# LPCB235_-_POWER_MANAGEMENT.net
KiCad netlist of a schematic drawn in Altium Designer
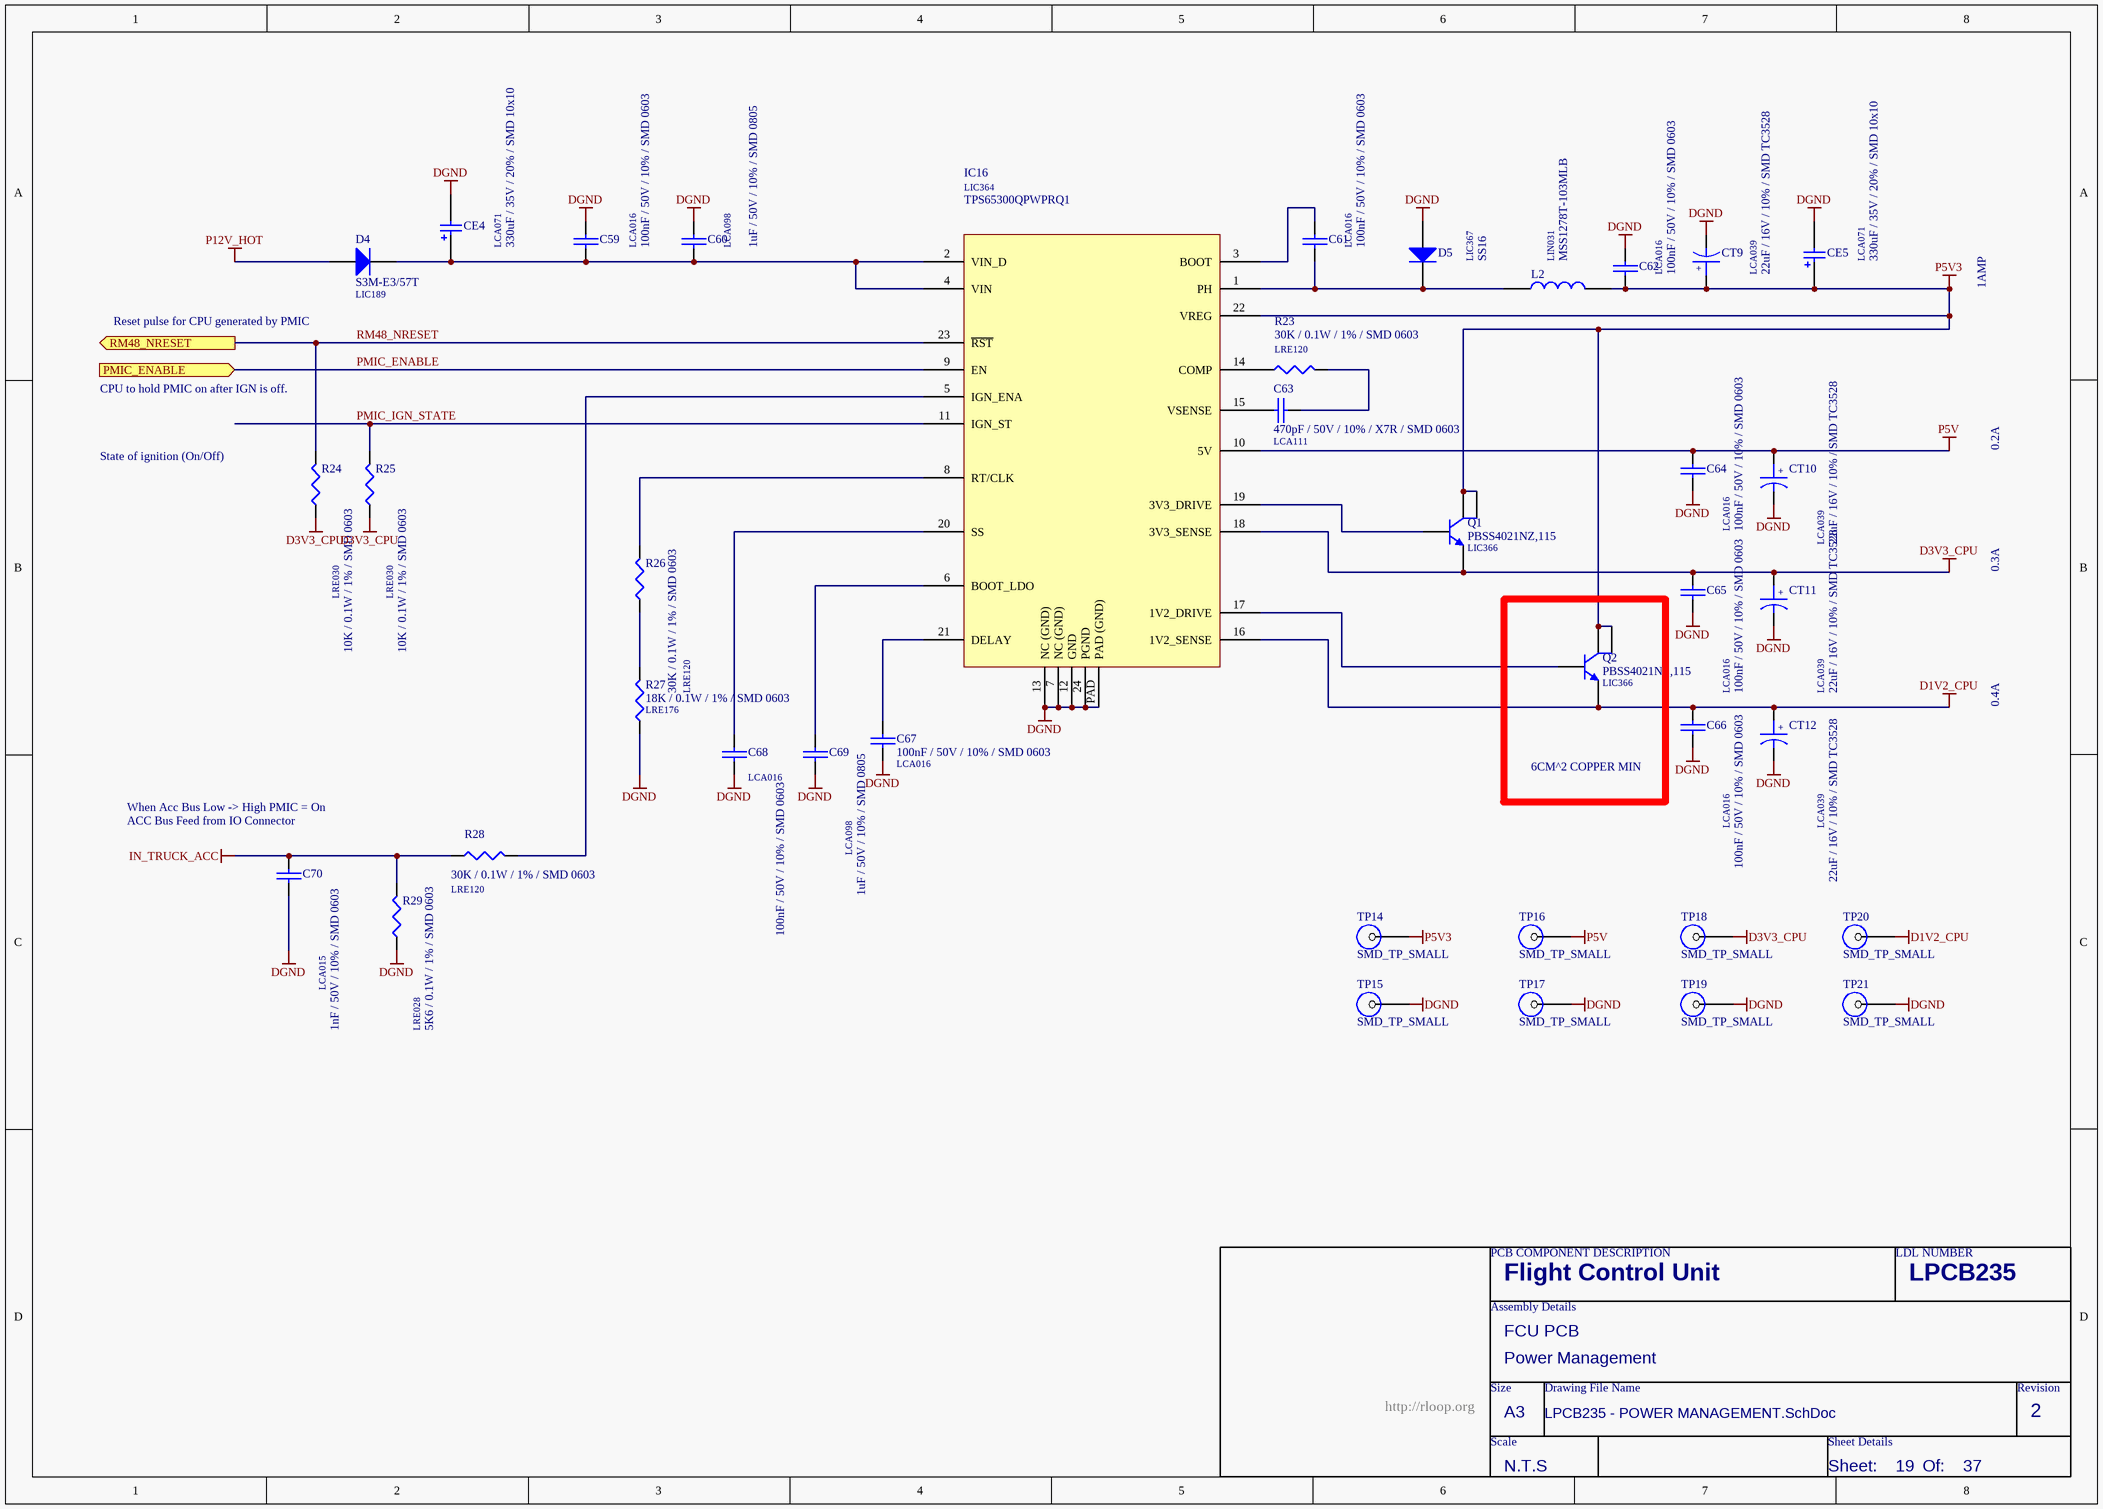
[diagram p0: LPCB235 - POWER MANAGEMENT.SchDoc]

(export (version "E")
  (design (tool "Eeschema 10.0.6"))
  (components
    (comp (ref "C59")
      (value "100nF / 50V / 10% / SMD 0603")
      (footprint "LFP011__CC1608-0603-IPC7351_B")
      (description "Capacitor, Ceramic Chip, 100nF (0.1uF), 50V, 5%, SMD 0603 [LCA016]")
      (fields (field (name "LDL_NUMBER") "LCA016"))
      (libsource (lib "LDL_Capacitors") (part "100nF / 50V / 10% / SMD 0603"))
    )
    (comp (ref "C60")
      (value "1uF / 50V / 10% / SMD 0805")
      (footprint "LFP010__CC2012-0805-IPC7351_B")
      (description "Capacitor, Ceramic Chip, 1uF, 50V, SMD 0805 [LCA098]")
      (fields (field (name "LDL_NUMBER") "LCA098"))
      (libsource (lib "LDL_Capacitors") (part "1uF / 50V / 10% / SMD 0805"))
    )
    (comp (ref "C61")
      (value "100nF / 50V / 10% / SMD 0603")
      (footprint "LFP011__CC1608-0603-IPC7351_B")
      (description "Capacitor, Ceramic Chip, 100nF (0.1uF), 50V, 5%, SMD 0603 [LCA016]")
      (fields (field (name "LDL_NUMBER") "LCA016"))
      (libsource (lib "LDL_Capacitors") (part "100nF / 50V / 10% / SMD 0603"))
    )
    (comp (ref "C62")
      (value "100nF / 50V / 10% / SMD 0603")
      (footprint "LFP011__CC1608-0603-IPC7351_B")
      (description "Capacitor, Ceramic Chip, 100nF (0.1uF), 50V, 5%, SMD 0603 [LCA016]")
      (fields (field (name "LDL_NUMBER") "LCA016"))
      (libsource (lib "LDL_Capacitors") (part "100nF / 50V / 10% / SMD 0603"))
    )
    (comp (ref "C63")
      (value "470pF / 50V / 10% / X7R / SMD 0603")
      (footprint "LFP011__CC1608-0603-IPC7351_B")
      (description "Capacitor, Ceramic Chip, 470pF, 50V, 10% X7R, SMD 0603 [LCA111]")
      (fields (field (name "LDL_NUMBER") "LCA111"))
      (libsource (lib "LDL_Capacitors") (part "470pF / 50V / 10% / X7R / SMD 0603"))
    )
    (comp (ref "C64")
      (value "100nF / 50V / 10% / SMD 0603")
      (footprint "LFP011__CC1608-0603-IPC7351_B")
      (description "Capacitor, Ceramic Chip, 100nF (0.1uF), 50V, 5%, SMD 0603 [LCA016]")
      (fields (field (name "LDL_NUMBER") "LCA016"))
      (libsource (lib "LDL_Capacitors") (part "100nF / 50V / 10% / SMD 0603"))
    )
    (comp (ref "C65")
      (value "100nF / 50V / 10% / SMD 0603")
      (footprint "LFP011__CC1608-0603-IPC7351_B")
      (description "Capacitor, Ceramic Chip, 100nF (0.1uF), 50V, 5%, SMD 0603 [LCA016]")
      (fields (field (name "LDL_NUMBER") "LCA016"))
      (libsource (lib "LDL_Capacitors") (part "100nF / 50V / 10% / SMD 0603"))
    )
    (comp (ref "C66")
      (value "100nF / 50V / 10% / SMD 0603")
      (footprint "LFP011__CC1608-0603-IPC7351_B")
      (description "Capacitor, Ceramic Chip, 100nF (0.1uF), 50V, 5%, SMD 0603 [LCA016]")
      (fields (field (name "LDL_NUMBER") "LCA016"))
      (libsource (lib "LDL_Capacitors") (part "100nF / 50V / 10% / SMD 0603"))
    )
    (comp (ref "C67")
      (value "100nF / 50V / 10% / SMD 0603")
      (footprint "LFP011__CC1608-0603-IPC7351_B")
      (description "Capacitor, Ceramic Chip, 100nF (0.1uF), 50V, 5%, SMD 0603 [LCA016]")
      (fields (field (name "LDL_NUMBER") "LCA016"))
      (libsource (lib "LDL_Capacitors") (part "100nF / 50V / 10% / SMD 0603"))
    )
    (comp (ref "C68")
      (value "100nF / 50V / 10% / SMD 0603")
      (footprint "LFP011__CC1608-0603-IPC7351_B")
      (description "Capacitor, Ceramic Chip, 100nF (0.1uF), 50V, 5%, SMD 0603 [LCA016]")
      (fields (field (name "LDL_NUMBER") "LCA016"))
      (libsource (lib "LDL_Capacitors") (part "100nF / 50V / 10% / SMD 0603"))
    )
    (comp (ref "C69")
      (value "1uF / 50V / 10% / SMD 0805")
      (footprint "LFP010__CC2012-0805-IPC7351_B")
      (description "Capacitor, Ceramic Chip, 1uF, 50V, SMD 0805 [LCA098]")
      (fields (field (name "LDL_NUMBER") "LCA098"))
      (libsource (lib "LDL_Capacitors") (part "1uF / 50V / 10% / SMD 0805"))
    )
    (comp (ref "C70")
      (value "1nF / 50V / 10% / SMD 0603")
      (footprint "LFP011__CC1608-0603-IPC7351_B")
      (description "Capacitor, Ceramic Chip, 1nF (1000pF), 50V, 10%, SMD 0603 [LCA015]")
      (fields (field (name "LDL_NUMBER") "LCA015"))
      (libsource (lib "LDL_Capacitors") (part "1nF / 50V / 10% / SMD 0603"))
    )
    (comp (ref "CE4")
      (value "330uF / 35V / 20% / SMD 10x10")
      (footprint "LFP041__NICHICON_WT_10X10")
      (description "Capacitor, Aluminum Electrolytic, 330uF, 35V, 20%, SMD (10mm x 10mm)")
      (fields (field (name "LDL_NUMBER") "LCA071"))
      (libsource (lib "LDL_Capacitors") (part "330uF / 35V / 20% / SMD 10x10"))
    )
    (comp (ref "CE5")
      (value "330uF / 35V / 20% / SMD 10x10")
      (footprint "LFP041__NICHICON_WT_10X10")
      (description "Capacitor, Aluminum Electrolytic, 330uF, 35V, 20%, SMD (10mm x 10mm)")
      (fields (field (name "LDL_NUMBER") "LCA071"))
      (libsource (lib "LDL_Capacitors") (part "330uF / 35V / 20% / SMD 10x10"))
    )
    (comp (ref "CT9")
      (value "22uF / 16V / 10% / SMD TC3528")
      (footprint "LFP018__TC3528")
      (description "Capacitor, Tantalum, 22uF, 16V, 10%, SMD TC3528 (BCASE) [LCA039]")
      (fields (field (name "LDL_NUMBER") "LCA039"))
      (libsource (lib "LDL_Capacitors") (part "22uF / 16V / 10% / SMD TC3528"))
    )
    (comp (ref "CT10")
      (value "22uF / 16V / 10% / SMD TC3528")
      (footprint "LFP018__TC3528")
      (description "Capacitor, Tantalum, 22uF, 16V, 10%, SMD TC3528 (BCASE) [LCA039]")
      (fields (field (name "LDL_NUMBER") "LCA039"))
      (libsource (lib "LDL_Capacitors") (part "22uF / 16V / 10% / SMD TC3528"))
    )
    (comp (ref "CT11")
      (value "22uF / 16V / 10% / SMD TC3528")
      (footprint "LFP018__TC3528")
      (description "Capacitor, Tantalum, 22uF, 16V, 10%, SMD TC3528 (BCASE) [LCA039]")
      (fields (field (name "LDL_NUMBER") "LCA039"))
      (libsource (lib "LDL_Capacitors") (part "22uF / 16V / 10% / SMD TC3528"))
    )
    (comp (ref "CT12")
      (value "22uF / 16V / 10% / SMD TC3528")
      (footprint "LFP018__TC3528")
      (description "Capacitor, Tantalum, 22uF, 16V, 10%, SMD TC3528 (BCASE) [LCA039]")
      (fields (field (name "LDL_NUMBER") "LCA039"))
      (libsource (lib "LDL_Capacitors") (part "22uF / 16V / 10% / SMD TC3528"))
    )
    (comp (ref "D4")
      (value "S3M-E3/57T")
      (footprint "LFP040__DO-214AB")
      (description "Diode, General Purpose Rectifier, 3A, 200V, SMD DO-214AB [LIC189]")
      (fields (field (name "LDL_NUMBER") "LIC189"))
      (libsource (lib "LDL_Semiconductors") (part "S3M-E3/57T"))
    )
    (comp (ref "D5")
      (value "SS16")
      (footprint "LFP039__DO-214AC")
      (description "Diode, Schottky Rectifier, 60V, 1A, SMD DO-214AC [LIC367]")
      (fields (field (name "LDL_NUMBER") "LIC367"))
      (libsource (lib "LDL_Semiconductors") (part "SS16"))
    )
    (comp (ref "IC16")
      (value "TPS65300QPWPRQ1")
      (footprint "LFP036__R-PDSO-G24")
      (description "IC, Power Management IC, SMD [LIC364]")
      (fields (field (name "LDL_NUMBER") "LIC364"))
      (libsource (lib "LDL_Semiconductors") (part "TPS65300QPWPRQ1"))
    )
    (comp (ref "L2")
      (value "MSS1278T-103MLB")
      (footprint "LFP037__MSS1278T")
      (description "Inductor, 10uH, 20%, 5.7A, SMD [LIN031]")
      (fields (field (name "LDL_NUMBER") "LIN031"))
      (libsource (lib "LDL_Inductors") (part "MSS1278T-103MLB"))
    )
    (comp (ref "Q1")
      (value "PBSS4021NZ,115")
      (footprint "LFP038__SOT223-4M")
      (description "Transistor, NPN, 20V 8A 770mW 95MHz, SMD [LIC366]")
      (fields (field (name "LDL_NUMBER") "LIC366"))
      (libsource (lib "LDL_Semiconductors") (part "PBSS4021NZ,115"))
    )
    (comp (ref "Q2")
      (value "PBSS4021NZ,115")
      (footprint "LFP038__SOT223-4M")
      (description "Transistor, NPN, 20V 8A 770mW 95MHz, SMD [LIC366]")
      (fields (field (name "LDL_NUMBER") "LIC366"))
      (libsource (lib "LDL_Semiconductors") (part "PBSS4021NZ,115"))
    )
    (comp (ref "R23")
      (value "30K / 0.1W / 1% / SMD 0603")
      (footprint "LFP020__CR1608-0603-IPC7351_B")
      (description "Resistor, Ceramic Chip, 30K, 0.1W, 1%, SMD 0603 [LRE120]")
      (fields (field (name "LDL_NUMBER") "LRE120"))
      (libsource (lib "LDL_Resistors") (part "30K / 0.1W / 1% / SMD 0603"))
    )
    (comp (ref "R24")
      (value "10K / 0.1W / 1% / SMD 0603")
      (footprint "LFP020__CR1608-0603-IPC7351_B")
      (description "Resistor, Ceramic Chip, 10K, 0.1W, 1%, SMD 0603 [LRE030]")
      (fields (field (name "LDL_NUMBER") "LRE030"))
      (libsource (lib "LDL_Resistors") (part "10K / 0.1W / 1% / SMD 0603"))
    )
    (comp (ref "R25")
      (value "10K / 0.1W / 1% / SMD 0603")
      (footprint "LFP020__CR1608-0603-IPC7351_B")
      (description "Resistor, Ceramic Chip, 10K, 0.1W, 1%, SMD 0603 [LRE030]")
      (fields (field (name "LDL_NUMBER") "LRE030"))
      (libsource (lib "LDL_Resistors") (part "10K / 0.1W / 1% / SMD 0603"))
    )
    (comp (ref "R26")
      (value "30K / 0.1W / 1% / SMD 0603")
      (footprint "LFP020__CR1608-0603-IPC7351_B")
      (description "Resistor, Ceramic Chip, 30K, 0.1W, 1%, SMD 0603 [LRE120]")
      (fields (field (name "LDL_NUMBER") "LRE120"))
      (libsource (lib "LDL_Resistors") (part "30K / 0.1W / 1% / SMD 0603"))
    )
    (comp (ref "R27")
      (value "18K / 0.1W / 1% / SMD 0603")
      (footprint "LFP020__CR1608-0603-IPC7351_B")
      (description "Resistor, Ceramic Chip, 18K, 0.1W, 1%, SMD 0603 [LRE176]")
      (fields (field (name "LDL_NUMBER") "LRE176"))
      (libsource (lib "LDL_Resistors") (part "18K / 0.1W / 1% / SMD 0603"))
    )
    (comp (ref "R28")
      (value "30K / 0.1W / 1% / SMD 0603")
      (footprint "LFP020__CR1608-0603-IPC7351_B")
      (description "Resistor, Ceramic Chip, 30K, 0.1W, 1%, SMD 0603 [LRE120]")
      (fields (field (name "LDL_NUMBER") "LRE120"))
      (libsource (lib "LDL_Resistors") (part "30K / 0.1W / 1% / SMD 0603"))
    )
    (comp (ref "R29")
      (value "5K6 / 0.1W / 1% / SMD 0603")
      (footprint "LFP020__CR1608-0603-IPC7351_B")
      (description "Resistor, Ceramic Chip, 5.6K, 0.1W, 1%, SMD 0603 [LRE028]")
      (fields (field (name "LDL_NUMBER") "LRE028"))
      (libsource (lib "LDL_Resistors") (part "5K6 / 0.1W / 1% / SMD 0603"))
    )
    (comp (ref "TP14")
      (value "SMD_TP_SMALL")
      (footprint "SMD-TP-SMALL")
      (description "SMD Test Point")
      (libsource (lib "LDL_Connectors") (part "SMD_TP_SMALL"))
    )
    (comp (ref "TP15")
      (value "SMD_TP_SMALL")
      (footprint "SMD-TP-SMALL")
      (description "SMD Test Point")
      (libsource (lib "LDL_Connectors") (part "SMD_TP_SMALL"))
    )
    (comp (ref "TP16")
      (value "SMD_TP_SMALL")
      (footprint "SMD-TP-SMALL")
      (description "SMD Test Point")
      (libsource (lib "LDL_Connectors") (part "SMD_TP_SMALL"))
    )
    (comp (ref "TP17")
      (value "SMD_TP_SMALL")
      (footprint "SMD-TP-SMALL")
      (description "SMD Test Point")
      (libsource (lib "LDL_Connectors") (part "SMD_TP_SMALL"))
    )
    (comp (ref "TP18")
      (value "SMD_TP_SMALL")
      (footprint "SMD-TP-SMALL")
      (description "SMD Test Point")
      (libsource (lib "LDL_Connectors") (part "SMD_TP_SMALL"))
    )
    (comp (ref "TP19")
      (value "SMD_TP_SMALL")
      (footprint "SMD-TP-SMALL")
      (description "SMD Test Point")
      (libsource (lib "LDL_Connectors") (part "SMD_TP_SMALL"))
    )
    (comp (ref "TP20")
      (value "SMD_TP_SMALL")
      (footprint "SMD-TP-SMALL")
      (description "SMD Test Point")
      (libsource (lib "LDL_Connectors") (part "SMD_TP_SMALL"))
    )
    (comp (ref "TP21")
      (value "SMD_TP_SMALL")
      (footprint "SMD-TP-SMALL")
      (description "SMD Test Point")
      (libsource (lib "LDL_Connectors") (part "SMD_TP_SMALL"))
    )
  )
  (nets
    (net (code "1") (name "/PMIC_ENABLE") (class "Default")
      (node (ref "IC16") (pin "9") (pinfunction "EN_9") (pintype "passive"))
    )
    (net (code "2") (name "/PMIC_IGN_STATE") (class "Default")
      (node (ref "IC16") (pin "11") (pinfunction "IGN_ST_11") (pintype "passive"))
      (node (ref "R25") (pin "2") (pintype "passive"))
    )
    (net (code "3") (name "/RM48_NRESET") (class "Default")
      (node (ref "IC16") (pin "23") (pinfunction "~{RST}_23") (pintype "passive"))
      (node (ref "R24") (pin "2") (pintype "passive"))
    )
    (net (code "4") (name "D1V2_CPU") (class "Default")
      (node (ref "C66") (pin "1") (pintype "passive"))
      (node (ref "CT12") (pin "1") (pinfunction "1_1") (pintype "passive"))
      (node (ref "IC16") (pin "16") (pinfunction "1V2_SENSE_16") (pintype "passive"))
      (node (ref "Q2") (pin "3") (pinfunction "E_3") (pintype "passive"))
      (node (ref "TP20") (pin "1") (pintype "passive"))
    )
    (net (code "5") (name "D3V3_CPU") (class "Default")
      (node (ref "C65") (pin "1") (pintype "passive"))
      (node (ref "CT11") (pin "1") (pinfunction "1_1") (pintype "passive"))
      (node (ref "IC16") (pin "18") (pinfunction "3V3_SENSE_18") (pintype "passive"))
      (node (ref "Q1") (pin "3") (pinfunction "E_3") (pintype "passive"))
      (node (ref "R24") (pin "1") (pintype "passive"))
      (node (ref "R25") (pin "1") (pintype "passive"))
      (node (ref "TP18") (pin "1") (pintype "passive"))
    )
    (net (code "6") (name "DGND") (class "Default")
      (node (ref "C59") (pin "2") (pintype "passive"))
      (node (ref "C60") (pin "2") (pintype "passive"))
      (node (ref "C62") (pin "1") (pintype "passive"))
      (node (ref "C64") (pin "2") (pintype "passive"))
      (node (ref "C65") (pin "2") (pintype "passive"))
      (node (ref "C66") (pin "2") (pintype "passive"))
      (node (ref "C67") (pin "2") (pintype "passive"))
      (node (ref "C68") (pin "1") (pintype "passive"))
      (node (ref "C69") (pin "2") (pintype "passive"))
      (node (ref "C70") (pin "2") (pintype "passive"))
      (node (ref "CE4") (pin "2") (pinfunction "2_2") (pintype "passive"))
      (node (ref "CE5") (pin "2") (pinfunction "2_2") (pintype "passive"))
      (node (ref "CT10") (pin "2") (pinfunction "2_2") (pintype "passive"))
      (node (ref "CT11") (pin "2") (pinfunction "2_2") (pintype "passive"))
      (node (ref "CT12") (pin "2") (pinfunction "2_2") (pintype "passive"))
      (node (ref "CT9") (pin "2") (pinfunction "2_2") (pintype "passive"))
      (node (ref "D5") (pin "2") (pinfunction "A_2") (pintype "passive"))
      (node (ref "IC16") (pin "12") (pinfunction "GND_12") (pintype "power_in"))
      (node (ref "IC16") (pin "13") (pinfunction "NC_(GND)_13") (pintype "power_in"))
      (node (ref "IC16") (pin "24") (pinfunction "PGND_24") (pintype "power_in"))
      (node (ref "IC16") (pin "7") (pinfunction "NC_(GND)_7") (pintype "power_in"))
      (node (ref "IC16") (pin "PAD") (pinfunction "PAD_(GND)_PAD") (pintype "power_in"))
      (node (ref "R27") (pin "1") (pintype "passive"))
      (node (ref "R29") (pin "1") (pintype "passive"))
      (node (ref "TP15") (pin "1") (pintype "passive"))
      (node (ref "TP17") (pin "1") (pintype "passive"))
      (node (ref "TP19") (pin "1") (pintype "passive"))
      (node (ref "TP21") (pin "1") (pintype "passive"))
    )
    (net (code "7") (name "IN_TRUCK_ACC") (class "Default")
      (node (ref "C70") (pin "1") (pintype "passive"))
      (node (ref "R28") (pin "1") (pintype "passive"))
      (node (ref "R29") (pin "2") (pintype "passive"))
    )
    (net (code "8") (name "Net-(C63-Pad2)") (class "Default")
      (node (ref "C63") (pin "2") (pintype "passive"))
      (node (ref "R23") (pin "2") (pintype "passive"))
    )
    (net (code "9") (name "Net-(D4-K)") (class "Default")
      (node (ref "C59") (pin "1") (pintype "passive"))
      (node (ref "C60") (pin "1") (pintype "passive"))
      (node (ref "CE4") (pin "1") (pinfunction "1_1") (pintype "passive"))
      (node (ref "D4") (pin "1") (pinfunction "K_1") (pintype "passive"))
      (node (ref "IC16") (pin "2") (pinfunction "VIN_D_2") (pintype "passive"))
      (node (ref "IC16") (pin "4") (pinfunction "VIN_4") (pintype "passive"))
    )
    (net (code "10") (name "Net-(D5-K)") (class "Default")
      (node (ref "C61") (pin "1") (pintype "passive"))
      (node (ref "D5") (pin "1") (pinfunction "K_1") (pintype "passive"))
      (node (ref "IC16") (pin "1") (pinfunction "PH_1") (pintype "passive"))
      (node (ref "L2") (pin "1") (pinfunction "1_1") (pintype "passive"))
    )
    (net (code "11") (name "Net-(IC16-1V2_DRIVE)") (class "Default")
      (node (ref "IC16") (pin "17") (pinfunction "1V2_DRIVE_17") (pintype "passive"))
      (node (ref "Q2") (pin "1") (pinfunction "B_1") (pintype "passive"))
    )
    (net (code "12") (name "Net-(IC16-3V3_DRIVE)") (class "Default")
      (node (ref "IC16") (pin "19") (pinfunction "3V3_DRIVE_19") (pintype "passive"))
      (node (ref "Q1") (pin "1") (pinfunction "B_1") (pintype "passive"))
    )
    (net (code "13") (name "Net-(IC16-BOOT)") (class "Default")
      (node (ref "C61") (pin "2") (pintype "passive"))
      (node (ref "IC16") (pin "3") (pinfunction "BOOT_3") (pintype "passive"))
    )
    (net (code "14") (name "Net-(IC16-BOOT_LDO)") (class "Default")
      (node (ref "C69") (pin "1") (pintype "passive"))
      (node (ref "IC16") (pin "6") (pinfunction "BOOT_LDO_6") (pintype "passive"))
    )
    (net (code "15") (name "Net-(IC16-COMP)") (class "Default")
      (node (ref "IC16") (pin "14") (pinfunction "COMP_14") (pintype "passive"))
      (node (ref "R23") (pin "1") (pintype "passive"))
    )
    (net (code "16") (name "Net-(IC16-DELAY)") (class "Default")
      (node (ref "C67") (pin "1") (pintype "passive"))
      (node (ref "IC16") (pin "21") (pinfunction "DELAY_21") (pintype "passive"))
    )
    (net (code "17") (name "Net-(IC16-IGN_ENA)") (class "Default")
      (node (ref "IC16") (pin "5") (pinfunction "IGN_ENA_5") (pintype "passive"))
      (node (ref "R28") (pin "2") (pintype "passive"))
    )
    (net (code "18") (name "Net-(IC16-RT{slash}CLK)") (class "Default")
      (node (ref "IC16") (pin "8") (pinfunction "RT/CLK_8") (pintype "passive"))
      (node (ref "R26") (pin "2") (pintype "passive"))
    )
    (net (code "19") (name "Net-(IC16-SS)") (class "Default")
      (node (ref "C68") (pin "2") (pintype "passive"))
      (node (ref "IC16") (pin "20") (pinfunction "SS_20") (pintype "passive"))
    )
    (net (code "20") (name "Net-(IC16-VSENSE)") (class "Default")
      (node (ref "C63") (pin "1") (pintype "passive"))
      (node (ref "IC16") (pin "15") (pinfunction "VSENSE_15") (pintype "passive"))
    )
    (net (code "21") (name "Net-(R26-Pad1)") (class "Default")
      (node (ref "R26") (pin "1") (pintype "passive"))
      (node (ref "R27") (pin "2") (pintype "passive"))
    )
    (net (code "22") (name "P5V") (class "Default")
      (node (ref "C64") (pin "1") (pintype "passive"))
      (node (ref "CT10") (pin "1") (pinfunction "1_1") (pintype "passive"))
      (node (ref "IC16") (pin "10") (pinfunction "5V_10") (pintype "passive"))
      (node (ref "TP16") (pin "1") (pintype "passive"))
    )
    (net (code "23") (name "P5V3") (class "Default")
      (node (ref "C62") (pin "2") (pintype "passive"))
      (node (ref "CE5") (pin "1") (pinfunction "1_1") (pintype "passive"))
      (node (ref "CT9") (pin "1") (pinfunction "1_1") (pintype "passive"))
      (node (ref "IC16") (pin "22") (pinfunction "VREG_22") (pintype "passive"))
      (node (ref "L2") (pin "2") (pinfunction "2_2") (pintype "passive"))
      (node (ref "Q1") (pin "2") (pinfunction "C_2") (pintype "passive"))
      (node (ref "Q1") (pin "4") (pinfunction "C_4") (pintype "passive"))
      (node (ref "Q2") (pin "2") (pinfunction "C_2") (pintype "passive"))
      (node (ref "Q2") (pin "4") (pinfunction "C_4") (pintype "passive"))
      (node (ref "TP14") (pin "1") (pintype "passive"))
    )
    (net (code "24") (name "P12V_HOT") (class "Default")
      (node (ref "D4") (pin "2") (pinfunction "A_2") (pintype "passive"))
    )
  )
)
